# parakeet_board_rev_09.net
KiCad netlist of a schematic drawn in EAGLE
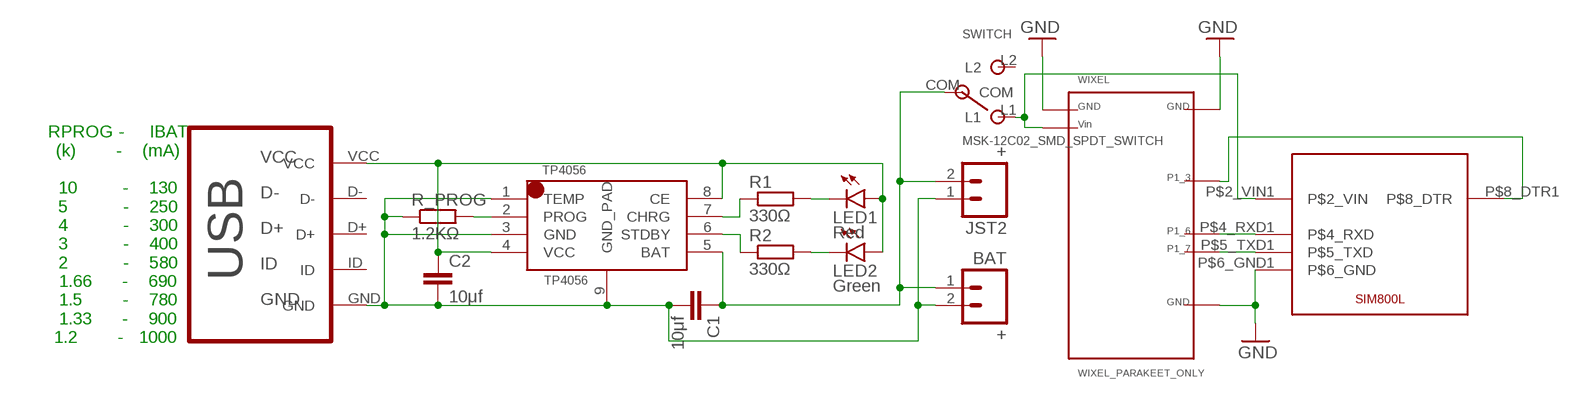
[diagram p0: schematic, sheet 1]

(export (version "E")
  (design (tool "Eeschema 10.0.6"))
  (components
    (comp (ref "+")
      (value "BAT")
      (footprint "eagle-import:1X02")
      (libsource (lib "eagle-import") (part "M02PTH"))
    )
    (comp (ref "C1")
      (value "10μf")
      (footprint "eagle-import:C1206")
      (libsource (lib "eagle-import") (part "C-EUC1206"))
    )
    (comp (ref "C2")
      (value "10μf")
      (footprint "eagle-import:C1206")
      (libsource (lib "eagle-import") (part "C-EUC1206"))
    )
    (comp (ref "JST2")
      (value "+")
      (footprint "eagle-import:JST-2-SMD")
      (libsource (lib "eagle-import") (part "M02-JST-2MM-SMT"))
    )
    (comp (ref "LED1")
      (value "Red")
      (footprint "eagle-import:LED-1206")
      (libsource (lib "eagle-import") (part "LED1206"))
    )
    (comp (ref "LED2")
      (value "Green")
      (footprint "eagle-import:LED-1206")
      (libsource (lib "eagle-import") (part "LED1206"))
    )
    (comp (ref "R1")
      (value "330Ω")
      (footprint "eagle-import:R1206")
      (libsource (lib "eagle-import") (part "R-EU_R1206"))
    )
    (comp (ref "R2")
      (value "330Ω")
      (footprint "eagle-import:R1206")
      (libsource (lib "eagle-import") (part "R-EU_R1206"))
    )
    (comp (ref "R_PROG")
      (value "1.2KΩ")
      (footprint "eagle-import:R1206")
      (libsource (lib "eagle-import") (part "R-EU_R1206"))
    )
    (comp (ref "SIM800L")
      (value "SIM800L_PARAKEET_ONLY")
      (footprint "eagle-import:SIM800L_PARAKEET_ONLY")
      (libsource (lib "eagle-import") (part "SIM800L_PARAKEET_ONLY"))
    )
    (comp (ref "SWITCH")
      (value "MSK-12C02_SMD_SPDT_SWITCH")
      (footprint "eagle-import:MSK-12C02")
      (libsource (lib "eagle-import") (part "MSK-12C02_SMD_SPDT_SWITCH"))
    )
    (comp (ref "TP4056")
      (value "TP4056")
      (footprint "eagle-import:SOP-8")
      (libsource (lib "eagle-import") (part "TP4056"))
    )
    (comp (ref "USB")
      (value "MICRO-USB-B")
      (footprint "eagle-import:MICRO_USB_4_LEGS")
      (libsource (lib "eagle-import") (part "MICRO-USB-B"))
    )
    (comp (ref "WIXEL")
      (value "WIXEL_PARAKEET_ONLY")
      (footprint "eagle-import:WIXEL_PARAKEET_ONLY")
      (libsource (lib "eagle-import") (part "WIXEL_PARAKEET_ONLY"))
    )
  )
  (nets
    (net (code "1") (name "GND") (class "Default")
      (node (ref "+") (pin "2") (pinfunction "2_2") (pintype "passive"))
      (node (ref "C1") (pin "2") (pinfunction "2_2") (pintype "passive"))
      (node (ref "C2") (pin "2") (pinfunction "2_2") (pintype "passive"))
      (node (ref "JST2") (pin "1") (pinfunction "2_1") (pintype "passive"))
      (node (ref "R_PROG") (pin "1") (pinfunction "1_1") (pintype "passive"))
      (node (ref "SIM800L") (pin "P$6_GND1") (pinfunction "P$6_GND_P$6_GND1") (pintype "bidirectional"))
      (node (ref "TP4056") (pin "1") (pinfunction "TEMP_1") (pintype "bidirectional"))
      (node (ref "TP4056") (pin "3") (pinfunction "GND_3") (pintype "bidirectional"))
      (node (ref "TP4056") (pin "9") (pinfunction "GND_PAD_9") (pintype "bidirectional"))
      (node (ref "USB") (pin "GND") (pinfunction "GND_GND") (pintype "bidirectional"))
      (node (ref "WIXEL") (pin "P$1") (pinfunction "P$1-GND1_P$1") (pintype "bidirectional"))
      (node (ref "WIXEL") (pin "P$12") (pinfunction "P$12-GND2_P$12") (pintype "bidirectional"))
      (node (ref "WIXEL") (pin "P$23") (pinfunction "P$23-GND3_P$23") (pintype "bidirectional"))
    )
    (net (code "2") (name "Net-(JST2-1)") (class "Default")
      (node (ref "+") (pin "1") (pinfunction "1_1") (pintype "passive"))
      (node (ref "C1") (pin "1") (pinfunction "1_1") (pintype "passive"))
      (node (ref "JST2") (pin "2") (pinfunction "1_2") (pintype "passive"))
      (node (ref "SWITCH") (pin "COM") (pinfunction "COM_COM") (pintype "bidirectional"))
      (node (ref "TP4056") (pin "5") (pinfunction "BAT_5") (pintype "bidirectional"))
    )
    (net (code "3") (name "Net-(LED1-PadC)") (class "Default")
      (node (ref "LED1") (pin "C") (pinfunction "C_C") (pintype "passive"))
      (node (ref "R1") (pin "2") (pinfunction "2_2") (pintype "passive"))
    )
    (net (code "4") (name "Net-(LED2-PadC)") (class "Default")
      (node (ref "LED2") (pin "C") (pinfunction "C_C") (pintype "passive"))
      (node (ref "R2") (pin "2") (pinfunction "2_2") (pintype "passive"))
    )
    (net (code "5") (name "Net-(SIM800L-P$2_VIN)") (class "Default")
      (node (ref "SIM800L") (pin "P$2_VIN1") (pinfunction "P$2_VIN_P$2_VIN1") (pintype "bidirectional"))
      (node (ref "SWITCH") (pin "L1") (pinfunction "L1_L1") (pintype "bidirectional"))
      (node (ref "WIXEL") (pin "P$2") (pinfunction "P$2-VIN_P$2") (pintype "bidirectional"))
    )
    (net (code "6") (name "Net-(SIM800L-P$4_RXD)") (class "Default")
      (node (ref "SIM800L") (pin "P$4_RXD1") (pinfunction "P$4_RXD_P$4_RXD1") (pintype "bidirectional"))
      (node (ref "WIXEL") (pin "P$19") (pinfunction "P$19-P1_6_P$19") (pintype "bidirectional"))
    )
    (net (code "7") (name "Net-(SIM800L-P$5_TXD)") (class "Default")
      (node (ref "SIM800L") (pin "P$5_TXD1") (pinfunction "P$5_TXD_P$5_TXD1") (pintype "bidirectional"))
      (node (ref "WIXEL") (pin "P$20") (pinfunction "P$20-P1_7_P$20") (pintype "bidirectional"))
    )
    (net (code "8") (name "Net-(SIM800L-P$8_DTR)") (class "Default")
      (node (ref "SIM800L") (pin "P$8_DTR1") (pinfunction "P$8_DTR_P$8_DTR1") (pintype "bidirectional"))
      (node (ref "WIXEL") (pin "P$16") (pinfunction "P$16-P1_3_P$16") (pintype "bidirectional"))
    )
    (net (code "9") (name "Net-(TP4056-CE)") (class "Default")
      (node (ref "C2") (pin "1") (pinfunction "1_1") (pintype "passive"))
      (node (ref "LED1") (pin "A") (pinfunction "A_A") (pintype "passive"))
      (node (ref "LED2") (pin "A") (pinfunction "A_A") (pintype "passive"))
      (node (ref "TP4056") (pin "4") (pinfunction "VCC_4") (pintype "bidirectional"))
      (node (ref "TP4056") (pin "8") (pinfunction "CE_8") (pintype "bidirectional"))
      (node (ref "USB") (pin "VCC") (pinfunction "VCC_VCC") (pintype "bidirectional"))
    )
    (net (code "10") (name "Net-(TP4056-CHRG)") (class "Default")
      (node (ref "R1") (pin "1") (pinfunction "1_1") (pintype "passive"))
      (node (ref "TP4056") (pin "7") (pinfunction "CHRG_7") (pintype "bidirectional"))
    )
    (net (code "11") (name "Net-(TP4056-PROG)") (class "Default")
      (node (ref "R_PROG") (pin "2") (pinfunction "2_2") (pintype "passive"))
      (node (ref "TP4056") (pin "2") (pinfunction "PROG_2") (pintype "bidirectional"))
    )
    (net (code "12") (name "Net-(TP4056-STDBY)") (class "Default")
      (node (ref "R2") (pin "1") (pinfunction "1_1") (pintype "passive"))
      (node (ref "TP4056") (pin "6") (pinfunction "STDBY_6") (pintype "bidirectional"))
    )
    (net (code "13") (name "unconnected-(SWITCH-PadL2)") (class "Default")
      (node (ref "SWITCH") (pin "L2") (pinfunction "L2_L2") (pintype "bidirectional"))
    )
    (net (code "14") (name "unconnected-(USB-PadD+)") (class "Default")
      (node (ref "USB") (pin "D+") (pinfunction "D+_D+") (pintype "bidirectional"))
    )
    (net (code "15") (name "unconnected-(USB-PadD-)") (class "Default")
      (node (ref "USB") (pin "D-") (pinfunction "D-_D-") (pintype "bidirectional"))
    )
    (net (code "16") (name "unconnected-(USB-PadID)") (class "Default")
      (node (ref "USB") (pin "ID") (pinfunction "ID_ID") (pintype "bidirectional"))
    )
  )
)
